# Main.net
KiCad netlist of a schematic drawn in Altium Designer
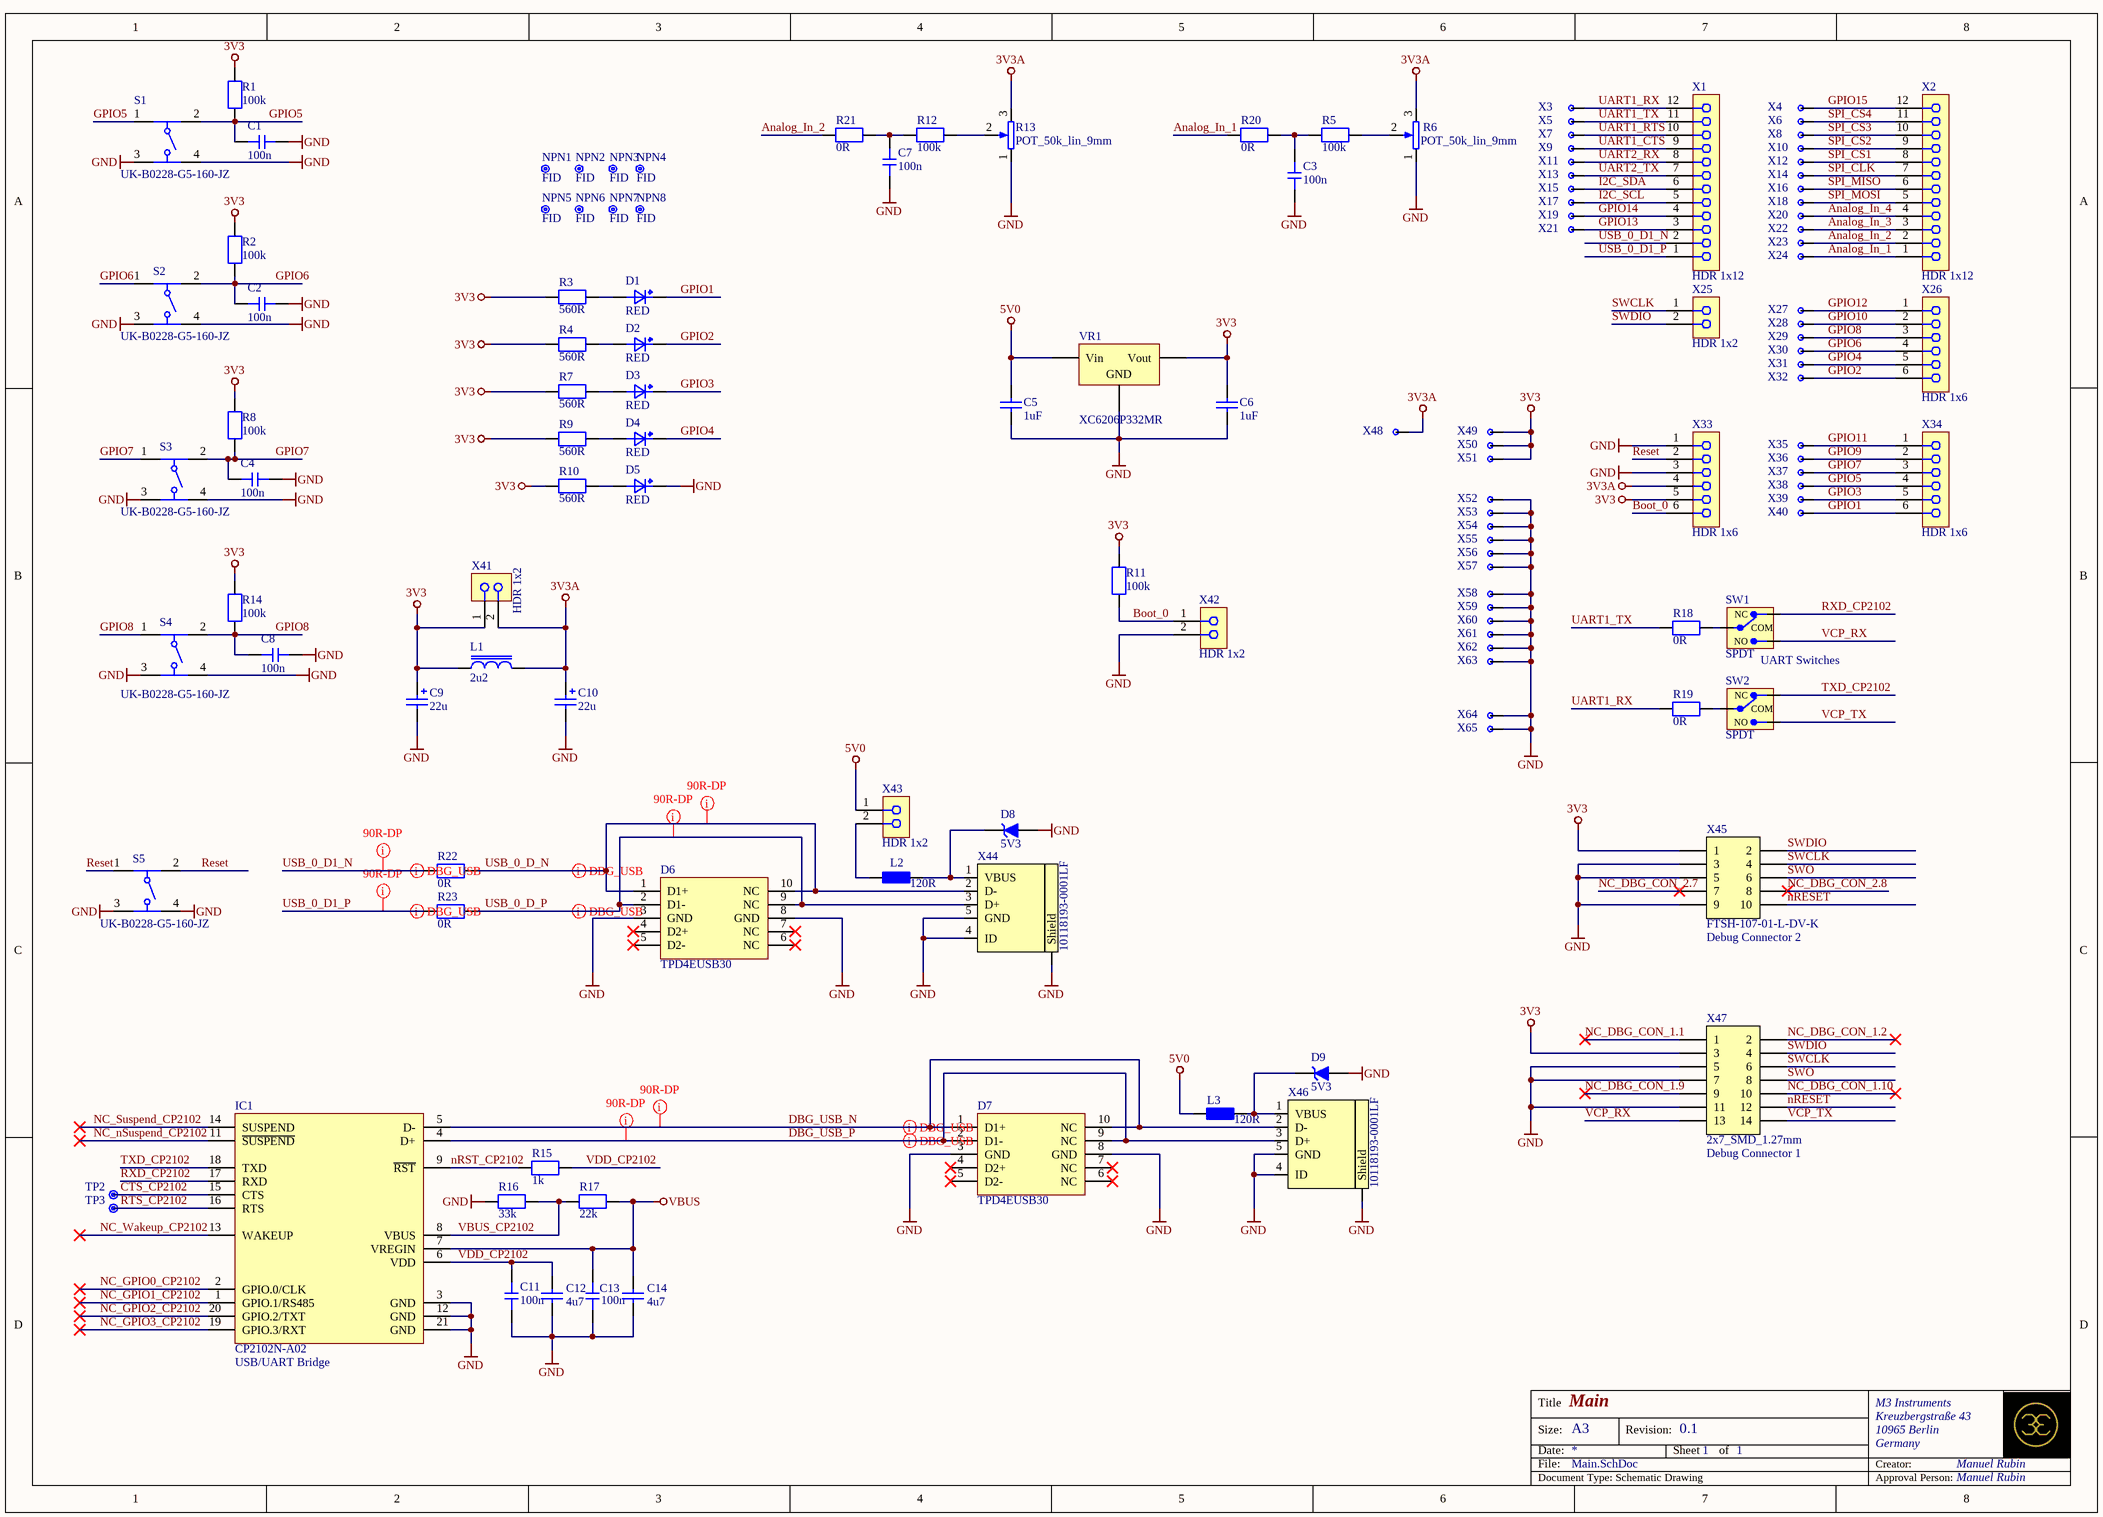
[diagram p0: Main.SchDoc]

(export (version "E")
  (design (tool "Eeschema 10.0.6"))
  (components
    (comp (ref "C1")
      (value "100n")
      (footprint "CAPC1608X95N")
      (description "100n_50V")
      (fields (field (name "MANUFACTURER") "AVX") (field (name "MANUFACTURER PART NUMBER") "06031C104KAT2A"))
      (libsource (lib "Raindancer") (part "C_100n_50V_0603"))
    )
    (comp (ref "C2")
      (value "100n")
      (footprint "CAPC1608X95N")
      (description "100n_50V")
      (fields (field (name "MANUFACTURER") "AVX") (field (name "MANUFACTURER PART NUMBER") "06031C104KAT2A"))
      (libsource (lib "Raindancer") (part "C_100n_50V_0603"))
    )
    (comp (ref "C3")
      (value "100n")
      (footprint "CAPC1608X95N")
      (description "100n_50V")
      (fields (field (name "MANUFACTURER") "AVX") (field (name "MANUFACTURER PART NUMBER") "06031C104KAT2A"))
      (libsource (lib "CAPN_100nF_50V_0603") (part "100n_50V"))
    )
    (comp (ref "C4")
      (value "100n")
      (footprint "CAPC1608X95N")
      (description "100n_50V")
      (fields (field (name "MANUFACTURER") "AVX") (field (name "MANUFACTURER PART NUMBER") "06031C104KAT2A"))
      (libsource (lib "Raindancer") (part "C_100n_50V_0603"))
    )
    (comp (ref "C5")
      (value "1uF")
      (footprint "0603_C")
      (description "Chip capacitors")
      (fields
        (field (name "MANUFACTURER") "Samsung Electro-Mechanics")
        (field (name "PARTNUMBER") "CL10A105KB8NNNC")
      )
      (libsource (lib "Cap") (part "0603 1uF (105) 10% 50V"))
    )
    (comp (ref "C6")
      (value "1uF")
      (footprint "0603_C")
      (description "Chip capacitors")
      (fields
        (field (name "MANUFACTURER") "Samsung Electro-Mechanics")
        (field (name "PARTNUMBER") "CL10A105KB8NNNC")
      )
      (libsource (lib "Cap") (part "0603 1uF (105) 10% 50V"))
    )
    (comp (ref "C7")
      (value "100n")
      (footprint "CAPC1608X95N")
      (description "100n_50V")
      (fields (field (name "MANUFACTURER") "AVX") (field (name "MANUFACTURER PART NUMBER") "06031C104KAT2A"))
      (libsource (lib "CAPN_100nF_50V_0603") (part "100n_50V"))
    )
    (comp (ref "C8")
      (value "100n")
      (footprint "CAPC1608X95N")
      (description "100n_50V")
      (fields (field (name "MANUFACTURER") "AVX") (field (name "MANUFACTURER PART NUMBER") "06031C104KAT2A"))
      (libsource (lib "Raindancer") (part "C_100n_50V_0603"))
    )
    (comp (ref "C9")
      (value "22u")
      (footprint "CAPAE4643X54M")
      (description "Aluminium Electrolytic Capacitors - SMD 22UF 16V HA SMD")
      (fields
        (field (name "MANUFACTURER") "Panasonic")
        (field (name "MANUFACTURER PART NUMBER") "EEE-HAC220WAR")
      )
      (libsource (lib "Caps") (part "CAP_22u"))
    )
    (comp (ref "C10")
      (value "22u")
      (footprint "CAPAE4643X54M")
      (description "Aluminium Electrolytic Capacitors - SMD 22UF 16V HA SMD")
      (fields
        (field (name "MANUFACTURER") "Panasonic")
        (field (name "MANUFACTURER PART NUMBER") "EEE-HAC220WAR")
      )
      (libsource (lib "Caps") (part "CAP_22u"))
    )
    (comp (ref "C11")
      (value "100n")
      (footprint "CAPC1608X95N")
      (description "100n_50V")
      (fields (field (name "MANUFACTURER") "AVX") (field (name "MANUFACTURER PART NUMBER") "06031C104KAT2A"))
      (libsource (lib "Raindancer") (part "C_100n_50V_0603"))
    )
    (comp (ref "C12")
      (value "4u7")
      (footprint "CAPC1608X95N")
      (description "16V 4.7uF X5R ±10% 0603 Multilayer Ceramic Capacitors MLCC - SMD/SMT ROHS")
      (fields
        (field (name "MANUFACTURER") "Murata Electronics")
        (field (name "MANUFACTURER PART NUMBER") "GRM188C81C475KE11D")
      )
      (libsource (lib "Caps") (part "CAP_4u7_0603"))
    )
    (comp (ref "C13")
      (value "100n")
      (footprint "CAPC1608X95N")
      (description "100n_50V")
      (fields (field (name "MANUFACTURER") "AVX") (field (name "MANUFACTURER PART NUMBER") "06031C104KAT2A"))
      (libsource (lib "Raindancer") (part "C_100n_50V_0603"))
    )
    (comp (ref "C14")
      (value "4u7")
      (footprint "CAPC1608X95N")
      (description "16V 4.7uF X5R ±10% 0603 Multilayer Ceramic Capacitors MLCC - SMD/SMT ROHS")
      (fields
        (field (name "MANUFACTURER") "Murata Electronics")
        (field (name "MANUFACTURER PART NUMBER") "GRM188C81C475KE11D")
      )
      (libsource (lib "Caps") (part "CAP_4u7_0603"))
    )
    (comp (ref "D1")
      (value "RED")
      (footprint "WL-SMCW_0805")
      (description "Standard LEDs - SMD WL-SMCW SMDMono TpVw Waterclr 0805 Red")
      (fields
        (field (name "MANUFACTURER") "Wurth Elektronik")
        (field (name "MANUFACTURER PART NUMBER") "150080RS75000")
      )
      (libsource (lib "Diodes") (part "LED_0805_RED_AK"))
    )
    (comp (ref "D2")
      (value "RED")
      (footprint "WL-SMCW_0805")
      (description "Standard LEDs - SMD WL-SMCW SMDMono TpVw Waterclr 0805 Red")
      (fields
        (field (name "MANUFACTURER") "Wurth Elektronik")
        (field (name "MANUFACTURER PART NUMBER") "150080RS75000")
      )
      (libsource (lib "Diodes") (part "LED_0805_RED_AK"))
    )
    (comp (ref "D3")
      (value "RED")
      (footprint "WL-SMCW_0805")
      (description "Standard LEDs - SMD WL-SMCW SMDMono TpVw Waterclr 0805 Red")
      (fields
        (field (name "MANUFACTURER") "Wurth Elektronik")
        (field (name "MANUFACTURER PART NUMBER") "150080RS75000")
      )
      (libsource (lib "Diodes") (part "LED_0805_RED_AK"))
    )
    (comp (ref "D4")
      (value "RED")
      (footprint "WL-SMCW_0805")
      (description "Standard LEDs - SMD WL-SMCW SMDMono TpVw Waterclr 0805 Red")
      (fields
        (field (name "MANUFACTURER") "Wurth Elektronik")
        (field (name "MANUFACTURER PART NUMBER") "150080RS75000")
      )
      (libsource (lib "Diodes") (part "LED_0805_RED_AK"))
    )
    (comp (ref "D5")
      (value "RED")
      (footprint "WL-SMCW_0805")
      (description "Standard LEDs - SMD WL-SMCW SMDMono TpVw Waterclr 0805 Red")
      (fields
        (field (name "MANUFACTURER") "Wurth Elektronik")
        (field (name "MANUFACTURER PART NUMBER") "150080RS75000")
      )
      (libsource (lib "Diodes") (part "LED_0805_RED_AK"))
    )
    (comp (ref "D6")
      (value "TPD4EUSB30")
      (footprint "DQA R-PUSON-N10")
      (description "2-, 4-Channel ESD Protection for Super-Speed USB 3.0 Interface")
      (fields
        (field (name "MANUFACTURER") "Texas Instruments")
        (field (name "MANUFACTURER PART NUMBER") "TPD4EUSB30DQAR")
      )
      (libsource (lib "TPD4EUSB30") (part "TPD4EUSB30DQAR"))
    )
    (comp (ref "D7")
      (value "TPD4EUSB30")
      (footprint "DQA R-PUSON-N10")
      (description "2-, 4-Channel ESD Protection for Super-Speed USB 3.0 Interface")
      (fields
        (field (name "MANUFACTURER") "Texas Instruments")
        (field (name "MANUFACTURER PART NUMBER") "TPD4EUSB30DQAR")
      )
      (libsource (lib "TPD4EUSB30") (part "TPD4EUSB30DQAR"))
    )
    (comp (ref "D8")
      (value "5V3")
      (footprint "SODFL100X40-2N")
      (description "ESD Suppressors / TVS Diodes WE-VE 0603 USB 2.0 5V 10MoHM")
      (fields
        (field (name "MANUFACTURER") "onsemi")
        (field (name "MANUFACTURER PART NUMBER") "SZESD7371P2T5G")
      )
      (libsource (lib "Diodes") (part "DIO_TVS_5V3"))
    )
    (comp (ref "D9")
      (value "5V3")
      (footprint "SODFL100X40-2N")
      (description "ESD Suppressors / TVS Diodes WE-VE 0603 USB 2.0 5V 10MoHM")
      (fields
        (field (name "MANUFACTURER") "onsemi")
        (field (name "MANUFACTURER PART NUMBER") "SZESD7371P2T5G")
      )
      (libsource (lib "Diodes") (part "DIO_TVS_5V3"))
    )
    (comp (ref "IC1")
      (value "CP2102N-A02")
      (footprint "SILABS_CP2102N-A02-GQFN20R")
      (description "USB Interface IC USBXpress - USB to UART Bridge QFN28")
      (fields
        (field (name "MANUFACTURER") "Silicon Labs")
        (field (name "MANUFACTURER PART NUMBER") "CP2102N-A02-GQFN20R")
        (field (name "DEVNOTE") "USB/UART Bridge")
      )
      (libsource (lib "Raindancer") (part "IC_CP2102N-A02-QFN20"))
    )
    (comp (ref "L1")
      (value "2u2")
      (footprint "INDP5050X39N")
      (description "Fixed Inductors 2.2uH 3.8A")
      (fields
        (field (name "MANUFACTURER") "Bourns")
        (field (name "MANUFACTURER PART NUMBER") "SRN5040TA-2R2M")
      )
      (libsource (lib "Inductors") (part "IND_2u2_3.8A"))
    )
    (comp (ref "L2")
      (value "120R")
      (footprint "INDC1608X95AN")
      (description "Chip Bead Inductors for Power Lines")
      (fields
        (field (name "MANUFACTURER") "Taiyo Yuden")
        (field (name "MANUFACTURER PART NUMBER") "FBMH1608HL121-T")
      )
      (libsource (lib "FB_120R_0603") (part "FB_120R_0603"))
    )
    (comp (ref "L3")
      (value "120R")
      (footprint "INDC1608X95AN")
      (description "Chip Bead Inductors for Power Lines")
      (fields
        (field (name "MANUFACTURER") "Taiyo Yuden")
        (field (name "MANUFACTURER PART NUMBER") "FBMH1608HL121-T")
      )
      (libsource (lib "FB_120R_0603") (part "FB_120R_0603"))
    )
    (comp (ref "NPN1")
      (value "FID")
      (footprint "Fiducial_1mm")
      (libsource (lib "MISC") (part "Fiducial_1mm"))
    )
    (comp (ref "NPN2")
      (value "FID")
      (footprint "Fiducial_1mm")
      (libsource (lib "MISC") (part "Fiducial_1mm"))
    )
    (comp (ref "NPN3")
      (value "FID")
      (footprint "Fiducial_1mm")
      (libsource (lib "MISC") (part "Fiducial_1mm"))
    )
    (comp (ref "NPN4")
      (value "FID")
      (footprint "Fiducial_1mm")
      (libsource (lib "MISC") (part "Fiducial_1mm"))
    )
    (comp (ref "NPN5")
      (value "FID")
      (footprint "Fiducial_1mm")
      (libsource (lib "MISC") (part "Fiducial_1mm"))
    )
    (comp (ref "NPN6")
      (value "FID")
      (footprint "Fiducial_1mm")
      (libsource (lib "MISC") (part "Fiducial_1mm"))
    )
    (comp (ref "NPN7")
      (value "FID")
      (footprint "Fiducial_1mm")
      (libsource (lib "MISC") (part "Fiducial_1mm"))
    )
    (comp (ref "NPN8")
      (value "FID")
      (footprint "Fiducial_1mm")
      (libsource (lib "MISC") (part "Fiducial_1mm"))
    )
    (comp (ref "R1")
      (value "100k")
      (footprint "RESC2012X70N")
      (description "Thick Film Resistors - SMD 1/8watt 100Kohms 1% 100ppm")
      (fields
        (field (name "MANUFACTURER") "Vishay / Dale")
        (field (name "MANUFACTURER PART NUMBER") "CRCW0805100KFKEA")
      )
      (libsource (lib "Resistors") (part "RES_100k_0805"))
    )
    (comp (ref "R2")
      (value "100k")
      (footprint "RESC2012X70N")
      (description "Thick Film Resistors - SMD 1/8watt 100Kohms 1% 100ppm")
      (fields
        (field (name "MANUFACTURER") "Vishay / Dale")
        (field (name "MANUFACTURER PART NUMBER") "CRCW0805100KFKEA")
      )
      (libsource (lib "Resistors") (part "RES_100k_0805"))
    )
    (comp (ref "R3")
      (value "560R")
      (footprint "RESC2012X70N")
      (description "Thick Film Resistors - SMD 560 Ohms 125 mW 0805 1%")
      (fields
        (field (name "MANUFACTURER") "YAGEO")
        (field (name "MANUFACTURER PART NUMBER") "RC0805FR-10560RL")
      )
      (libsource (lib "Resistors") (part "RES_560R_0805"))
    )
    (comp (ref "R4")
      (value "560R")
      (footprint "RESC2012X70N")
      (description "Thick Film Resistors - SMD 560 Ohms 125 mW 0805 1%")
      (fields
        (field (name "MANUFACTURER") "YAGEO")
        (field (name "MANUFACTURER PART NUMBER") "RC0805FR-10560RL")
      )
      (libsource (lib "Resistors") (part "RES_560R_0805"))
    )
    (comp (ref "R5")
      (value "100k")
      (footprint "RESC2012X70N")
      (description "Thick Film Resistors - SMD 1/8watt 100Kohms 1% 100ppm")
      (fields
        (field (name "MANUFACTURER") "Vishay / Dale")
        (field (name "MANUFACTURER PART NUMBER") "CRCW0805100KFKEA")
      )
      (libsource (lib "") (part "RES_100k_0805_1"))
    )
    (comp (ref "R6")
      (value "POT_50k_lin_9mm")
      (footprint "PTV09")
      (description "Potentiometers PANEL CONTROL - 9MM-ST-CA 50 kohms 30 mm")
      (fields
        (field (name "MANUFACTURER") "Bourns")
        (field (name "MANUFACTURER PART NUMBER") "PTV09A-4030S-A503")
      )
      (libsource (lib "Resistors") (part "POT_50k_lin_9mm"))
    )
    (comp (ref "R7")
      (value "560R")
      (footprint "RESC2012X70N")
      (description "Thick Film Resistors - SMD 560 Ohms 125 mW 0805 1%")
      (fields
        (field (name "MANUFACTURER") "YAGEO")
        (field (name "MANUFACTURER PART NUMBER") "RC0805FR-10560RL")
      )
      (libsource (lib "Resistors") (part "RES_560R_0805"))
    )
    (comp (ref "R8")
      (value "100k")
      (footprint "RESC2012X70N")
      (description "Thick Film Resistors - SMD 1/8watt 100Kohms 1% 100ppm")
      (fields
        (field (name "MANUFACTURER") "Vishay / Dale")
        (field (name "MANUFACTURER PART NUMBER") "CRCW0805100KFKEA")
      )
      (libsource (lib "Resistors") (part "RES_100k_0805"))
    )
    (comp (ref "R9")
      (value "560R")
      (footprint "RESC2012X70N")
      (description "Thick Film Resistors - SMD 560 Ohms 125 mW 0805 1%")
      (fields
        (field (name "MANUFACTURER") "YAGEO")
        (field (name "MANUFACTURER PART NUMBER") "RC0805FR-10560RL")
      )
      (libsource (lib "Resistors") (part "RES_560R_0805"))
    )
    (comp (ref "R10")
      (value "560R")
      (footprint "RESC2012X70N")
      (description "Thick Film Resistors - SMD 560 Ohms 125 mW 0805 1%")
      (fields
        (field (name "MANUFACTURER") "YAGEO")
        (field (name "MANUFACTURER PART NUMBER") "RC0805FR-10560RL")
      )
      (libsource (lib "Resistors") (part "RES_560R_0805"))
    )
    (comp (ref "R11")
      (value "100k")
      (footprint "RESC2012X70N")
      (description "Thick Film Resistors - SMD 1/8watt 100Kohms 1% 100ppm")
      (fields
        (field (name "MANUFACTURER") "Vishay / Dale")
        (field (name "MANUFACTURER PART NUMBER") "CRCW0805100KFKEA")
      )
      (libsource (lib "Resistors") (part "RES_100k_0805"))
    )
    (comp (ref "R12")
      (value "100k")
      (footprint "RESC2012X70N")
      (description "Thick Film Resistors - SMD 1/8watt 100Kohms 1% 100ppm")
      (fields
        (field (name "MANUFACTURER") "Vishay / Dale")
        (field (name "MANUFACTURER PART NUMBER") "CRCW0805100KFKEA")
      )
      (libsource (lib "") (part "RES_100k_0805_1"))
    )
    (comp (ref "R13")
      (value "POT_50k_lin_9mm")
      (footprint "PTV09")
      (description "Potentiometers PANEL CONTROL - 9MM-ST-CA 50 kohms 30 mm")
      (fields
        (field (name "MANUFACTURER") "Bourns")
        (field (name "MANUFACTURER PART NUMBER") "PTV09A-4030S-A503")
      )
      (libsource (lib "Resistors") (part "POT_50k_lin_9mm"))
    )
    (comp (ref "R14")
      (value "100k")
      (footprint "RESC2012X70N")
      (description "Thick Film Resistors - SMD 1/8watt 100Kohms 1% 100ppm")
      (fields
        (field (name "MANUFACTURER") "Vishay / Dale")
        (field (name "MANUFACTURER PART NUMBER") "CRCW0805100KFKEA")
      )
      (libsource (lib "Resistors") (part "RES_100k_0805"))
    )
    (comp (ref "R15")
      (value "1k")
      (footprint "RESC1608X55AN")
      (description "Thick Film Resistors - SMD 1 kOhms 100mW 0603 1%")
      (fields
        (field (name "MANUFACTURER") "Yageo")
        (field (name "MANUFACTURER PART NUMBER") "RC0603FR-071KL")
      )
      (libsource (lib "Raindancer") (part "RES_1k_0603"))
    )
    (comp (ref "R16")
      (value "33k")
      (footprint "RESC1608X55AN")
      (description "Thick Film Resistors - SMD 33 kOhms 100 mW 0603 5%")
      (fields
        (field (name "MANUFACTURER") "YAGEO")
        (field (name "MANUFACTURER PART NUMBER") "RC0603JR-0733KL")
      )
      (libsource (lib "Raindancer") (part "RES_33k_0603"))
    )
    (comp (ref "R17")
      (value "22k")
      (footprint "RESC1608X55AN")
      (description "Thick Film Resistors - SMD 22kOhms 1/10W 0603 1%")
      (fields
        (field (name "MANUFACTURER") "YAGEO")
        (field (name "MANUFACTURER PART NUMBER") "RC0603FR-7W22KL")
      )
      (libsource (lib "Raindancer") (part "RES_22k_0603"))
    )
    (comp (ref "R18")
      (value "0R")
      (footprint "RESC1608X55N")
      (description "Thick Film Resistors - SMD 1/10watt ZEROohm Jumper")
      (fields
        (field (name "MANUFACTURER") "Vishay")
        (field (name "MANUFACTURER PART NUMBER") "CRCW06030000Z0EA")
      )
      (libsource (lib "Resistors") (part "RES_0R_0603"))
    )
    (comp (ref "R19")
      (value "0R")
      (footprint "RESC1608X55N")
      (description "Thick Film Resistors - SMD 1/10watt ZEROohm Jumper")
      (fields
        (field (name "MANUFACTURER") "Vishay")
        (field (name "MANUFACTURER PART NUMBER") "CRCW06030000Z0EA")
      )
      (libsource (lib "Resistors") (part "RES_0R_0603"))
    )
    (comp (ref "R20")
      (value "0R")
      (footprint "RESC1608X55N")
      (description "Thick Film Resistors - SMD 1/10watt ZEROohm Jumper")
      (fields
        (field (name "MANUFACTURER") "Vishay")
        (field (name "MANUFACTURER PART NUMBER") "CRCW06030000Z0EA")
      )
      (libsource (lib "Resistors") (part "RES_0R_0603"))
    )
    (comp (ref "R21")
      (value "0R")
      (footprint "RESC1608X55N")
      (description "Thick Film Resistors - SMD 1/10watt ZEROohm Jumper")
      (fields
        (field (name "MANUFACTURER") "Vishay")
        (field (name "MANUFACTURER PART NUMBER") "CRCW06030000Z0EA")
      )
      (libsource (lib "Resistors") (part "RES_0R_0603"))
    )
    (comp (ref "R22")
      (value "0R")
      (footprint "RESC1608X55N")
      (description "Thick Film Resistors - SMD 1/10watt ZEROohm Jumper")
      (fields
        (field (name "MANUFACTURER") "Vishay")
        (field (name "MANUFACTURER PART NUMBER") "CRCW06030000Z0EA")
      )
      (libsource (lib "Resistors") (part "RES_0R_0603"))
    )
    (comp (ref "R23")
      (value "0R")
      (footprint "RESC1608X55N")
      (description "Thick Film Resistors - SMD 1/10watt ZEROohm Jumper")
      (fields
        (field (name "MANUFACTURER") "Vishay")
        (field (name "MANUFACTURER PART NUMBER") "CRCW06030000Z0EA")
      )
      (libsource (lib "Resistors") (part "RES_0R_0603"))
    )
    (comp (ref "S1")
      (value "UK-B0228-G5-160-JZ")
      (footprint "UK-B0228-G5-160-JZ")
      (fields (field (name "MANUFACTURER") "USAKRO"))
      (libsource (lib "Switches") (part "SW_UK-B0228-G5-160-JZ"))
    )
    (comp (ref "S2")
      (value "UK-B0228-G5-160-JZ")
      (footprint "UK-B0228-G5-160-JZ")
      (fields (field (name "MANUFACTURER") "USAKRO"))
      (libsource (lib "Switches") (part "SW_UK-B0228-G5-160-JZ"))
    )
    (comp (ref "S3")
      (value "UK-B0228-G5-160-JZ")
      (footprint "UK-B0228-G5-160-JZ")
      (fields (field (name "MANUFACTURER") "USAKRO"))
      (libsource (lib "Switches") (part "SW_UK-B0228-G5-160-JZ"))
    )
    (comp (ref "S4")
      (value "UK-B0228-G5-160-JZ")
      (footprint "UK-B0228-G5-160-JZ")
      (fields (field (name "MANUFACTURER") "USAKRO"))
      (libsource (lib "Switches") (part "SW_UK-B0228-G5-160-JZ"))
    )
    (comp (ref "S5")
      (value "UK-B0228-G5-160-JZ")
      (footprint "UK-B0228-G5-160-JZ")
      (fields (field (name "MANUFACTURER") "USAKRO"))
      (libsource (lib "Switches") (part "SW_UK-B0228-G5-160-JZ"))
    )
    (comp (ref "SW1")
      (value "SPDT")
      (footprint "SW_JS102011JCQN")
      (description "Slide Switch SPDT Surface Mount")
      (fields
        (field (name "MANUFACTURER") "C&K")
        (field (name "MANUFACTURER PART NUMBER") "JS102011JCQN")
        (field (name "DEVNOTE") "UART Switches")
      )
      (libsource (lib "Raindancer") (part "SW_JS102011JCQN"))
    )
    (comp (ref "SW2")
      (value "SPDT")
      (footprint "SW_JS102011JCQN")
      (description "Slide Switch SPDT Surface Mount")
      (fields (field (name "MANUFACTURER") "C&K") (field (name "MANUFACTURER PART NUMBER") "JS102011JCQN"))
      (libsource (lib "Raindancer") (part "SW_JS102011JCQN"))
    )
    (comp (ref "TP2")
      (value "TP 0.7mm")
      (footprint "TP_0.7mm")
      (description "Test Pad surface mount")
      (libsource (lib "Raindancer") (part "MISC_Test Pad 0.7mm"))
    )
    (comp (ref "TP3")
      (value "TP 0.7mm")
      (footprint "TP_0.7mm")
      (description "Test Pad surface mount")
      (libsource (lib "Raindancer") (part "MISC_Test Pad 0.7mm"))
    )
    (comp (ref "VR1")
      (value "XC6206P332MR")
      (footprint "SOT-23-3L")
      (description "低压差线性稳压(LDO)")
      (libsource (lib "LDO") (part "SOT-23 XC6206P332MR"))
    )
    (comp (ref "X1")
      (value "HDR 1x12")
      (footprint "61301211821_NO")
      (description "Board-to-Board-Steckverbinder, 2.54 mm, 12 Kontakt(e), Stiftleiste 1-Reihig")
      (fields (field (name "MANUFACTURER") "WE") (field (name "MANUFACTURER PART NUMBER") "61301211821"))
      (libsource (lib "Connectors") (part "CON_HEADER_1X12_FEMALE_NO"))
    )
    (comp (ref "X2")
      (value "HDR 1x12")
      (footprint "61301211821_NO")
      (description "Board-to-Board-Steckverbinder, 2.54 mm, 12 Kontakt(e), Stiftleiste 1-Reihig")
      (fields (field (name "MANUFACTURER") "WE") (field (name "MANUFACTURER PART NUMBER") "61301211821"))
      (libsource (lib "Connectors") (part "CON_HEADER_1X12_FEMALE_NO"))
    )
    (comp (ref "X3") (value "PAD") (footprint "PAD_1.1_1.6") (libsource (lib "MISC") (part "PAD_2.54")))
    (comp (ref "X4") (value "PAD") (footprint "PAD_1.1_1.6") (libsource (lib "MISC") (part "PAD_2.54")))
    (comp (ref "X5") (value "PAD") (footprint "PAD_1.1_1.6") (libsource (lib "MISC") (part "PAD_2.54")))
    (comp (ref "X6") (value "PAD") (footprint "PAD_1.1_1.6") (libsource (lib "MISC") (part "PAD_2.54")))
    (comp (ref "X7") (value "PAD") (footprint "PAD_1.1_1.6") (libsource (lib "MISC") (part "PAD_2.54")))
    (comp (ref "X8") (value "PAD") (footprint "PAD_1.1_1.6") (libsource (lib "MISC") (part "PAD_2.54")))
    (comp (ref "X9") (value "PAD") (footprint "PAD_1.1_1.6") (libsource (lib "MISC") (part "PAD_2.54")))
    (comp (ref "X10") (value "PAD") (footprint "PAD_1.1_1.6") (libsource (lib "MISC") (part "PAD_2.54")))
    (comp (ref "X11") (value "PAD") (footprint "PAD_1.1_1.6") (libsource (lib "MISC") (part "PAD_2.54")))
    (comp (ref "X12") (value "PAD") (footprint "PAD_1.1_1.6") (libsource (lib "MISC") (part "PAD_2.54")))
    (comp (ref "X13") (value "PAD") (footprint "PAD_1.1_1.6") (libsource (lib "MISC") (part "PAD_2.54")))
    (comp (ref "X14") (value "PAD") (footprint "PAD_1.1_1.6") (libsource (lib "MISC") (part "PAD_2.54")))
    (comp (ref "X15") (value "PAD") (footprint "PAD_1.1_1.6") (libsource (lib "MISC") (part "PAD_2.54")))
    (comp (ref "X16") (value "PAD") (footprint "PAD_1.1_1.6") (libsource (lib "MISC") (part "PAD_2.54")))
    (comp (ref "X17") (value "PAD") (footprint "PAD_1.1_1.6") (libsource (lib "MISC") (part "PAD_2.54")))
    (comp (ref "X18") (value "PAD") (footprint "PAD_1.1_1.6") (libsource (lib "MISC") (part "PAD_2.54")))
    (comp (ref "X19") (value "PAD") (footprint "PAD_1.1_1.6") (libsource (lib "MISC") (part "PAD_2.54")))
    (comp (ref "X20") (value "PAD") (footprint "PAD_1.1_1.6") (libsource (lib "MISC") (part "PAD_2.54")))
    (comp (ref "X21") (value "PAD") (footprint "PAD_1.1_1.6") (libsource (lib "MISC") (part "PAD_2.54")))
    (comp (ref "X22") (value "PAD") (footprint "PAD_1.1_1.6") (libsource (lib "MISC") (part "PAD_2.54")))
    (comp (ref "X23") (value "PAD") (footprint "PAD_1.1_1.6") (libsource (lib "MISC") (part "PAD_2.54")))
    (comp (ref "X24") (value "PAD") (footprint "PAD_1.1_1.6") (libsource (lib "MISC") (part "PAD_2.54")))
    (comp (ref "X25")
      (value "HDR 1x2")
      (footprint "61300211821_NO")
      (description "Board-to-Board-Steckverbinder, 2.54 mm, 2 Kontakt(e), Stiftleiste 1-Reihig")
      (fields (field (name "MANUFACTURER") "WE") (field (name "MANUFACTURER PART NUMBER") "61300211821"))
      (libsource (lib "Connectors") (part "CON_HEADER_1X2_FEMALE_NO"))
    )
    (comp (ref "X26")
      (value "HDR 1x6")
      (footprint "61300611821_NO")
      (description "Board-to-Board-Steckverbinder, 2.54 mm, 6 Kontakt(e), Stiftleiste 1-Reihig")
      (fields (field (name "MANUFACTURER") "WE") (field (name "MANUFACTURER PART NUMBER") "61300611821"))
      (libsource (lib "Connectors") (part "CON_HEADER_1X6_FEMALE_NO"))
    )
    (comp (ref "X27") (value "PAD") (footprint "PAD_1.1_1.6") (libsource (lib "MISC") (part "PAD_2.54")))
    (comp (ref "X28") (value "PAD") (footprint "PAD_1.1_1.6") (libsource (lib "MISC") (part "PAD_2.54")))
    (comp (ref "X29") (value "PAD") (footprint "PAD_1.1_1.6") (libsource (lib "MISC") (part "PAD_2.54")))
    (comp (ref "X30") (value "PAD") (footprint "PAD_1.1_1.6") (libsource (lib "MISC") (part "PAD_2.54")))
    (comp (ref "X31") (value "PAD") (footprint "PAD_1.1_1.6") (libsource (lib "MISC") (part "PAD_2.54")))
    (comp (ref "X32") (value "PAD") (footprint "PAD_1.1_1.6") (libsource (lib "MISC") (part "PAD_2.54")))
    (comp (ref "X33")
      (value "HDR 1x6")
      (footprint "61300611821_NO")
      (description "Board-to-Board-Steckverbinder, 2.54 mm, 6 Kontakt(e), Stiftleiste 1-Reihig")
      (fields (field (name "MANUFACTURER") "WE") (field (name "MANUFACTURER PART NUMBER") "61300611821"))
      (libsource (lib "Connectors") (part "CON_HEADER_1X6_FEMALE_NO"))
    )
    (comp (ref "X34")
      (value "HDR 1x6")
      (footprint "61300611821_NO")
      (description "Board-to-Board-Steckverbinder, 2.54 mm, 6 Kontakt(e), Stiftleiste 1-Reihig")
      (fields (field (name "MANUFACTURER") "WE") (field (name "MANUFACTURER PART NUMBER") "61300611821"))
      (libsource (lib "Connectors") (part "CON_HEADER_1X6_FEMALE_NO"))
    )
    (comp (ref "X35") (value "PAD") (footprint "PAD_1.1_1.6") (libsource (lib "MISC") (part "PAD_2.54")))
    (comp (ref "X36") (value "PAD") (footprint "PAD_1.1_1.6") (libsource (lib "MISC") (part "PAD_2.54")))
    (comp (ref "X37") (value "PAD") (footprint "PAD_1.1_1.6") (libsource (lib "MISC") (part "PAD_2.54")))
    (comp (ref "X38") (value "PAD") (footprint "PAD_1.1_1.6") (libsource (lib "MISC") (part "PAD_2.54")))
    (comp (ref "X39") (value "PAD") (footprint "PAD_1.1_1.6") (libsource (lib "MISC") (part "PAD_2.54")))
    (comp (ref "X40") (value "PAD") (footprint "PAD_1.1_1.6") (libsource (lib "MISC") (part "PAD_2.54")))
    (comp (ref "X41")
      (value "HDR 1x2")
      (footprint "CON_HEADER2.54_1x2W")
      (description "Board-to-Board-Steckverbinder, 2.54 mm, 2 Kontakt(e), Stiftleiste 1-Reihig")
      (fields
        (field (name "MANUFACTURER") "Samtec")
        (field (name "MANUFACTURER PART NUMBER") "TSW-102-07-T-S")
      )
      (libsource (lib "") (part "CON_HEADER_1X2_1"))
    )
    (comp (ref "X42")
      (value "HDR 1x2")
      (footprint "CON_HEADER2.54_1x2W")
      (description "Board-to-Board-Steckverbinder, 2.54 mm, 2 Kontakt(e), Stiftleiste 1-Reihig")
      (fields
        (field (name "MANUFACTURER") "Samtec")
        (field (name "MANUFACTURER PART NUMBER") "TSW-102-07-T-S")
      )
      (libsource (lib "Connectors") (part "CON_HEADER_1X2"))
    )
    (comp (ref "X43")
      (value "HDR 1x2")
      (footprint "CON_HEADER2.54_1x2W")
      (description "Board-to-Board-Steckverbinder, 2.54 mm, 2 Kontakt(e), Stiftleiste 1-Reihig")
      (fields
        (field (name "MANUFACTURER") "Samtec")
        (field (name "MANUFACTURER PART NUMBER") "TSW-102-07-T-S")
      )
      (libsource (lib "Connectors") (part "CON_HEADER_1X2"))
    )
    (comp (ref "X44")
      (value "10118193-0001LF")
      (footprint "USB-Micro-B-RA-SMD-PiP")
      (description "MicroUSB-B-SMT")
      (fields (field (name "MANUFACTURER") "Amphenol ICC (FCI)"))
      (libsource (lib "Connectors") (part "CON_MiniUSB-AB-SMT"))
    )
    (comp (ref "X45")
      (value "FTSH-107-01-L-DV-K")
      (footprint "HDR_2x5-SMD-1.27mm-K")
      (description "Pin Header 2x5, 1.27mm (50mil), SMD, Keying Shroud")
      (fields
        (field (name "MANUFACTURER") "Samtec")
        (field (name "MANUFACTURER PART NUMBER") "FTSH-105-01-L-DV-K")
        (field (name "DEVNOTE") "Debug Connector 2")
      )
      (libsource (lib "Raindancer") (part "CON_2x5_SMD_1.27mm"))
    )
    (comp (ref "X46")
      (value "10118193-0001LF")
      (footprint "USB-Micro-B-RA-SMD-PiP")
      (description "MicroUSB-B-SMT")
      (fields (field (name "MANUFACTURER") "Amphenol ICC (FCI)"))
      (libsource (lib "Connectors") (part "CON_MiniUSB-AB-SMT"))
    )
    (comp (ref "X47")
      (value "2x7_SMD_1.27mm")
      (footprint "FTSH-107-01-L-DV-K")
      (description "Headers & Wire Housings High Reliability Header Strips, 0.050 pitch, 2 x 7")
      (fields
        (field (name "MANUFACTURER") "Samtec")
        (field (name "MANUFACTURER PART NUMBER") "FTSH-107-04-F-DV-P-TR")
        (field (name "DEVNOTE") "Debug Connector 1")
      )
      (libsource (lib "Raindancer") (part "CON_2x7_SMD_1.27mm"))
    )
    (comp (ref "X48") (value "PAD") (footprint "PAD_1.1_1.6") (libsource (lib "MISC") (part "PAD_2.54")))
    (comp (ref "X49") (value "PAD") (footprint "PAD_1.1_1.6") (libsource (lib "MISC") (part "PAD_2.54")))
    (comp (ref "X50") (value "PAD") (footprint "PAD_1.1_1.6") (libsource (lib "MISC") (part "PAD_2.54")))
    (comp (ref "X51") (value "PAD") (footprint "PAD_1.1_1.6") (libsource (lib "MISC") (part "PAD_2.54")))
    (comp (ref "X52") (value "PAD") (footprint "PAD_1.1_1.6") (libsource (lib "MISC") (part "PAD_2.54")))
    (comp (ref "X53") (value "PAD") (footprint "PAD_1.1_1.6") (libsource (lib "MISC") (part "PAD_2.54")))
    (comp (ref "X54") (value "PAD") (footprint "PAD_1.1_1.6") (libsource (lib "MISC") (part "PAD_2.54")))
    (comp (ref "X55") (value "PAD") (footprint "PAD_1.1_1.6") (libsource (lib "MISC") (part "PAD_2.54")))
    (comp (ref "X56") (value "PAD") (footprint "PAD_1.1_1.6") (libsource (lib "MISC") (part "PAD_2.54")))
    (comp (ref "X57") (value "PAD") (footprint "PAD_1.1_1.6") (libsource (lib "MISC") (part "PAD_2.54")))
    (comp (ref "X58") (value "PAD") (footprint "PAD_1.1_1.6") (libsource (lib "MISC") (part "PAD_2.54")))
    (comp (ref "X59") (value "PAD") (footprint "PAD_1.1_1.6") (libsource (lib "MISC") (part "PAD_2.54")))
    (comp (ref "X60") (value "PAD") (footprint "PAD_1.1_1.6") (libsource (lib "MISC") (part "PAD_2.54")))
    (comp (ref "X61") (value "PAD") (footprint "PAD_1.1_1.6") (libsource (lib "MISC") (part "PAD_2.54")))
    (comp (ref "X62") (value "PAD") (footprint "PAD_1.1_1.6") (libsource (lib "MISC") (part "PAD_2.54")))
    (comp (ref "X63") (value "PAD") (footprint "PAD_1.1_1.6") (libsource (lib "MISC") (part "PAD_2.54")))
    (comp (ref "X64") (value "PAD") (footprint "PAD_1.1_1.6") (libsource (lib "MISC") (part "PAD_2.54")))
    (comp (ref "X65") (value "PAD") (footprint "PAD_1.1_1.6") (libsource (lib "MISC") (part "PAD_2.54")))
  )
  (nets
    (net (code "1") (name "/Analog_In_1") (class "Default")
      (node (ref "R20") (pin "2") (pinfunction "2_2") (pintype "passive"))
      (node (ref "X2") (pin "1") (pinfunction "1_1") (pintype "passive"))
      (node (ref "X24") (pin "1") (pinfunction "1_1") (pintype "passive"))
    )
    (net (code "2") (name "/Analog_In_2") (class "Default")
      (node (ref "R21") (pin "2") (pinfunction "2_2") (pintype "passive"))
      (node (ref "X2") (pin "2") (pinfunction "2_2") (pintype "passive"))
      (node (ref "X23") (pin "1") (pinfunction "1_1") (pintype "passive"))
    )
    (net (code "3") (name "/Analog_In_3") (class "Default")
      (node (ref "X2") (pin "3") (pinfunction "3_3") (pintype "passive"))
      (node (ref "X22") (pin "1") (pinfunction "1_1") (pintype "passive"))
    )
    (net (code "4") (name "/Analog_In_4") (class "Default")
      (node (ref "X2") (pin "4") (pinfunction "4_4") (pintype "passive"))
      (node (ref "X20") (pin "1") (pinfunction "1_1") (pintype "passive"))
    )
    (net (code "5") (name "/Boot_0") (class "Default")
      (node (ref "R11") (pin "1") (pinfunction "1_1") (pintype "passive"))
      (node (ref "X33") (pin "6") (pinfunction "6_6") (pintype "passive"))
      (node (ref "X42") (pin "1") (pinfunction "1_1") (pintype "passive"))
    )
    (net (code "6") (name "/CTS_CP2102") (class "Default")
      (node (ref "IC1") (pin "15") (pinfunction "CTS_15") (pintype "passive"))
      (node (ref "TP2") (pin "1") (pinfunction "1_1") (pintype "passive"))
    )
    (net (code "7") (name "/DBG_USB_N") (class "Default")
      (node (ref "D7") (pin "1") (pinfunction "D1+_1") (pintype "passive"))
      (node (ref "D7") (pin "10") (pinfunction "NC_10") (pintype "passive"))
      (node (ref "IC1") (pin "5") (pinfunction "D-_5") (pintype "passive"))
      (node (ref "X46") (pin "2") (pinfunction "D-_2") (pintype "passive"))
    )
    (net (code "8") (name "/DBG_USB_P") (class "Default")
      (node (ref "D7") (pin "2") (pinfunction "D1-_2") (pintype "passive"))
      (node (ref "D7") (pin "9") (pinfunction "NC_9") (pintype "passive"))
      (node (ref "IC1") (pin "4") (pinfunction "D+_4") (pintype "passive"))
      (node (ref "X46") (pin "3") (pinfunction "D+_3") (pintype "passive"))
    )
    (net (code "9") (name "/GPIO1") (class "Default")
      (node (ref "D1") (pin "K") (pinfunction "K_K") (pintype "passive"))
      (node (ref "X34") (pin "6") (pinfunction "6_6") (pintype "passive"))
      (node (ref "X40") (pin "1") (pinfunction "1_1") (pintype "passive"))
    )
    (net (code "10") (name "/GPIO2") (class "Default")
      (node (ref "D2") (pin "K") (pinfunction "K_K") (pintype "passive"))
      (node (ref "X26") (pin "6") (pinfunction "6_6") (pintype "passive"))
      (node (ref "X32") (pin "1") (pinfunction "1_1") (pintype "passive"))
    )
    (net (code "11") (name "/GPIO3") (class "Default")
      (node (ref "D3") (pin "K") (pinfunction "K_K") (pintype "passive"))
      (node (ref "X34") (pin "5") (pinfunction "5_5") (pintype "passive"))
      (node (ref "X39") (pin "1") (pinfunction "1_1") (pintype "passive"))
    )
    (net (code "12") (name "/GPIO4") (class "Default")
      (node (ref "D4") (pin "K") (pinfunction "K_K") (pintype "passive"))
      (node (ref "X26") (pin "5") (pinfunction "5_5") (pintype "passive"))
      (node (ref "X31") (pin "1") (pinfunction "1_1") (pintype "passive"))
    )
    (net (code "13") (name "/GPIO5") (class "Default")
      (node (ref "C1") (pin "1") (pinfunction "1_1") (pintype "passive"))
      (node (ref "R1") (pin "1") (pinfunction "1_1") (pintype "passive"))
      (node (ref "S1") (pin "1") (pinfunction "1_1") (pintype "passive"))
      (node (ref "S1") (pin "2") (pinfunction "2_2") (pintype "passive"))
      (node (ref "X34") (pin "4") (pinfunction "4_4") (pintype "passive"))
      (node (ref "X38") (pin "1") (pinfunction "1_1") (pintype "passive"))
    )
    (net (code "14") (name "/GPIO6") (class "Default")
      (node (ref "C2") (pin "1") (pinfunction "1_1") (pintype "passive"))
      (node (ref "R2") (pin "1") (pinfunction "1_1") (pintype "passive"))
      (node (ref "S2") (pin "1") (pinfunction "1_1") (pintype "passive"))
      (node (ref "S2") (pin "2") (pinfunction "2_2") (pintype "passive"))
      (node (ref "X26") (pin "4") (pinfunction "4_4") (pintype "passive"))
      (node (ref "X30") (pin "1") (pinfunction "1_1") (pintype "passive"))
    )
    (net (code "15") (name "/GPIO7") (class "Default")
      (node (ref "C4") (pin "1") (pinfunction "1_1") (pintype "passive"))
      (node (ref "R8") (pin "1") (pinfunction "1_1") (pintype "passive"))
      (node (ref "S3") (pin "1") (pinfunction "1_1") (pintype "passive"))
      (node (ref "S3") (pin "2") (pinfunction "2_2") (pintype "passive"))
      (node (ref "X34") (pin "3") (pinfunction "3_3") (pintype "passive"))
      (node (ref "X37") (pin "1") (pinfunction "1_1") (pintype "passive"))
    )
    (net (code "16") (name "/GPIO8") (class "Default")
      (node (ref "C8") (pin "1") (pinfunction "1_1") (pintype "passive"))
      (node (ref "R14") (pin "1") (pinfunction "1_1") (pintype "passive"))
      (node (ref "S4") (pin "1") (pinfunction "1_1") (pintype "passive"))
      (node (ref "S4") (pin "2") (pinfunction "2_2") (pintype "passive"))
      (node (ref "X26") (pin "3") (pinfunction "3_3") (pintype "passive"))
      (node (ref "X29") (pin "1") (pinfunction "1_1") (pintype "passive"))
    )
    (net (code "17") (name "/GPIO9") (class "Default")
      (node (ref "X34") (pin "2") (pinfunction "2_2") (pintype "passive"))
      (node (ref "X36") (pin "1") (pinfunction "1_1") (pintype "passive"))
    )
    (net (code "18") (name "/GPIO10") (class "Default")
      (node (ref "X26") (pin "2") (pinfunction "2_2") (pintype "passive"))
      (node (ref "X28") (pin "1") (pinfunction "1_1") (pintype "passive"))
    )
    (net (code "19") (name "/GPIO11") (class "Default")
      (node (ref "X34") (pin "1") (pinfunction "1_1") (pintype "passive"))
      (node (ref "X35") (pin "1") (pinfunction "1_1") (pintype "passive"))
    )
    (net (code "20") (name "/GPIO12") (class "Default")
      (node (ref "X26") (pin "1") (pinfunction "1_1") (pintype "passive"))
      (node (ref "X27") (pin "1") (pinfunction "1_1") (pintype "passive"))
    )
    (net (code "21") (name "/GPIO13") (class "Default")
      (node (ref "X1") (pin "3") (pinfunction "3_3") (pintype "passive"))
      (node (ref "X21") (pin "1") (pinfunction "1_1") (pintype "passive"))
    )
    (net (code "22") (name "/GPIO14") (class "Default")
      (node (ref "X1") (pin "4") (pinfunction "4_4") (pintype "passive"))
      (node (ref "X19") (pin "1") (pinfunction "1_1") (pintype "passive"))
    )
    (net (code "23") (name "/GPIO15") (class "Default")
      (node (ref "X2") (pin "12") (pinfunction "12_12") (pintype "passive"))
      (node (ref "X4") (pin "1") (pinfunction "1_1") (pintype "passive"))
    )
    (net (code "24") (name "/I2C_SCL") (class "Default")
      (node (ref "X1") (pin "5") (pinfunction "5_5") (pintype "passive"))
      (node (ref "X17") (pin "1") (pinfunction "1_1") (pintype "passive"))
    )
    (net (code "25") (name "/I2C_SDA") (class "Default")
      (node (ref "X1") (pin "6") (pinfunction "6_6") (pintype "passive"))
      (node (ref "X15") (pin "1") (pinfunction "1_1") (pintype "passive"))
    )
    (net (code "26") (name "/NC_DBG_CON_1.1") (class "Default")
      (node (ref "X47") (pin "1") (pinfunction "1_1") (pintype "passive+no_connect"))
    )
    (net (code "27") (name "/NC_DBG_CON_1.2") (class "Default")
      (node (ref "X47") (pin "2") (pinfunction "2_2") (pintype "passive+no_connect"))
    )
    (net (code "28") (name "/NC_DBG_CON_1.9") (class "Default")
      (node (ref "X47") (pin "9") (pinfunction "9_9") (pintype "passive+no_connect"))
    )
    (net (code "29") (name "/NC_DBG_CON_1.10") (class "Default")
      (node (ref "X47") (pin "10") (pinfunction "10_10") (pintype "passive+no_connect"))
    )
    (net (code "30") (name "/NC_DBG_CON_2.7") (class "Default")
      (node (ref "X45") (pin "7") (pinfunction "7_7") (pintype "passive+no_connect"))
    )
    (net (code "31") (name "/NC_DBG_CON_2.8") (class "Default")
      (node (ref "X45") (pin "8") (pinfunction "8_8") (pintype "passive+no_connect"))
    )
    (net (code "32") (name "/NC_GPIO0_CP2102") (class "Default")
      (node (ref "IC1") (pin "2") (pinfunction "GPIO.0/CLK_2") (pintype "passive+no_connect"))
    )
    (net (code "33") (name "/NC_GPIO1_CP2102") (class "Default")
      (node (ref "IC1") (pin "1") (pinfunction "GPIO.1/RS485_1") (pintype "passive+no_connect"))
    )
    (net (code "34") (name "/NC_GPIO2_CP2102") (class "Default")
      (node (ref "IC1") (pin "20") (pinfunction "GPIO.2/TXT_20") (pintype "passive+no_connect"))
    )
    (net (code "35") (name "/NC_GPIO3_CP2102") (class "Default")
      (node (ref "IC1") (pin "19") (pinfunction "GPIO.3/RXT_19") (pintype "passive+no_connect"))
    )
    (net (code "36") (name "/NC_Suspend_CP2102") (class "Default")
      (node (ref "IC1") (pin "14") (pinfunction "SUSPEND_14") (pintype "passive+no_connect"))
    )
    (net (code "37") (name "/NC_Wakeup_CP2102") (class "Default")
      (node (ref "IC1") (pin "13") (pinfunction "WAKEUP_13") (pintype "passive+no_connect"))
    )
    (net (code "38") (name "/NC_nSuspend_CP2102") (class "Default")
      (node (ref "IC1") (pin "11") (pinfunction "~{SUSPEND}_11") (pintype "passive+no_connect"))
    )
    (net (code "39") (name "/RTS_CP2102") (class "Default")
      (node (ref "IC1") (pin "16") (pinfunction "RTS_16") (pintype "passive"))
      (node (ref "TP3") (pin "1") (pinfunction "1_1") (pintype "passive"))
    )
    (net (code "40") (name "/RXD_CP2102") (class "Default")
      (node (ref "IC1") (pin "17") (pinfunction "RXD_17") (pintype "passive"))
      (node (ref "SW1") (pin "1") (pinfunction "NC_1") (pintype "passive"))
    )
    (net (code "41") (name "/Reset") (class "Default")
      (node (ref "S5") (pin "1") (pinfunction "1_1") (pintype "passive"))
      (node (ref "S5") (pin "2") (pinfunction "2_2") (pintype "passive"))
      (node (ref "X33") (pin "2") (pinfunction "2_2") (pintype "passive"))
    )
    (net (code "42") (name "/SPI_CLK") (class "Default")
      (node (ref "X14") (pin "1") (pinfunction "1_1") (pintype "passive"))
      (node (ref "X2") (pin "7") (pinfunction "7_7") (pintype "passive"))
    )
    (net (code "43") (name "/SPI_CS1") (class "Default")
      (node (ref "X12") (pin "1") (pinfunction "1_1") (pintype "passive"))
      (node (ref "X2") (pin "8") (pinfunction "8_8") (pintype "passive"))
    )
    (net (code "44") (name "/SPI_CS2") (class "Default")
      (node (ref "X10") (pin "1") (pinfunction "1_1") (pintype "passive"))
      (node (ref "X2") (pin "9") (pinfunction "9_9") (pintype "passive"))
    )
    (net (code "45") (name "/SPI_CS3") (class "Default")
      (node (ref "X2") (pin "10") (pinfunction "10_10") (pintype "passive"))
      (node (ref "X8") (pin "1") (pinfunction "1_1") (pintype "passive"))
    )
    (net (code "46") (name "/SPI_CS4") (class "Default")
      (node (ref "X2") (pin "11") (pinfunction "11_11") (pintype "passive"))
      (node (ref "X6") (pin "1") (pinfunction "1_1") (pintype "passive"))
    )
    (net (code "47") (name "/SPI_MISO") (class "Default")
      (node (ref "X16") (pin "1") (pinfunction "1_1") (pintype "passive"))
      (node (ref "X2") (pin "6") (pinfunction "6_6") (pintype "passive"))
    )
    (net (code "48") (name "/SPI_MOSI") (class "Default")
      (node (ref "X18") (pin "1") (pinfunction "1_1") (pintype "passive"))
      (node (ref "X2") (pin "5") (pinfunction "5_5") (pintype "passive"))
    )
    (net (code "49") (name "/SWCLK") (class "Default")
      (node (ref "X25") (pin "1") (pinfunction "1_1") (pintype "passive"))
      (node (ref "X45") (pin "4") (pinfunction "4_4") (pintype "passive"))
      (node (ref "X47") (pin "6") (pinfunction "6_6") (pintype "passive"))
    )
    (net (code "50") (name "/SWDIO") (class "Default")
      (node (ref "X25") (pin "2") (pinfunction "2_2") (pintype "passive"))
      (node (ref "X45") (pin "2") (pinfunction "2_2") (pintype "passive"))
      (node (ref "X47") (pin "4") (pinfunction "4_4") (pintype "passive"))
    )
    (net (code "51") (name "/SWO") (class "Default")
      (node (ref "X45") (pin "6") (pinfunction "6_6") (pintype "passive"))
      (node (ref "X47") (pin "8") (pinfunction "8_8") (pintype "passive"))
    )
    (net (code "52") (name "/TXD_CP2102") (class "Default")
      (node (ref "IC1") (pin "18") (pinfunction "TXD_18") (pintype "passive"))
      (node (ref "SW2") (pin "1") (pinfunction "NC_1") (pintype "passive"))
    )
    (net (code "53") (name "/UART1_CTS") (class "Default")
      (node (ref "X1") (pin "9") (pinfunction "9_9") (pintype "passive"))
      (node (ref "X9") (pin "1") (pinfunction "1_1") (pintype "passive"))
    )
    (net (code "54") (name "/UART1_RTS") (class "Default")
      (node (ref "X1") (pin "10") (pinfunction "10_10") (pintype "passive"))
      (node (ref "X7") (pin "1") (pinfunction "1_1") (pintype "passive"))
    )
    (net (code "55") (name "/UART1_RX") (class "Default")
      (node (ref "R19") (pin "2") (pinfunction "2_2") (pintype "passive"))
      (node (ref "X1") (pin "12") (pinfunction "12_12") (pintype "passive"))
      (node (ref "X3") (pin "1") (pinfunction "1_1") (pintype "passive"))
    )
    (net (code "56") (name "/UART1_TX") (class "Default")
      (node (ref "R18") (pin "2") (pinfunction "2_2") (pintype "passive"))
      (node (ref "X1") (pin "11") (pinfunction "11_11") (pintype "passive"))
      (node (ref "X5") (pin "1") (pinfunction "1_1") (pintype "passive"))
    )
    (net (code "57") (name "/UART2_RX") (class "Default")
      (node (ref "X1") (pin "8") (pinfunction "8_8") (pintype "passive"))
      (node (ref "X11") (pin "1") (pinfunction "1_1") (pintype "passive"))
    )
    (net (code "58") (name "/UART2_TX") (class "Default")
      (node (ref "X1") (pin "7") (pinfunction "7_7") (pintype "passive"))
      (node (ref "X13") (pin "1") (pinfunction "1_1") (pintype "passive"))
    )
    (net (code "59") (name "/USB_0_D1_N") (class "Default")
      (node (ref "R22") (pin "2") (pinfunction "2_2") (pintype "passive"))
      (node (ref "X1") (pin "2") (pinfunction "2_2") (pintype "passive"))
    )
    (net (code "60") (name "/USB_0_D1_P") (class "Default")
      (node (ref "R23") (pin "2") (pinfunction "2_2") (pintype "passive"))
      (node (ref "X1") (pin "1") (pinfunction "1_1") (pintype "passive"))
    )
    (net (code "61") (name "/USB_0_D_N") (class "Default")
      (node (ref "D6") (pin "1") (pinfunction "D1+_1") (pintype "passive"))
      (node (ref "D6") (pin "10") (pinfunction "NC_10") (pintype "passive"))
      (node (ref "R22") (pin "1") (pinfunction "1_1") (pintype "passive"))
      (node (ref "X44") (pin "2") (pinfunction "D-_2") (pintype "passive"))
    )
    (net (code "62") (name "/USB_0_D_P") (class "Default")
      (node (ref "D6") (pin "2") (pinfunction "D1-_2") (pintype "passive"))
      (node (ref "D6") (pin "9") (pinfunction "NC_9") (pintype "passive"))
      (node (ref "R23") (pin "1") (pinfunction "1_1") (pintype "passive"))
      (node (ref "X44") (pin "3") (pinfunction "D+_3") (pintype "passive"))
    )
    (net (code "63") (name "/VBUS_CP2102") (class "Default")
      (node (ref "IC1") (pin "8") (pinfunction "VBUS_8") (pintype "passive"))
      (node (ref "R16") (pin "1") (pinfunction "1_1") (pintype "passive"))
      (node (ref "R17") (pin "2") (pinfunction "2_2") (pintype "passive"))
    )
    (net (code "64") (name "/VCP_RX") (class "Default")
      (node (ref "SW1") (pin "3") (pinfunction "NO_3") (pintype "passive"))
      (node (ref "X47") (pin "13") (pinfunction "13_13") (pintype "passive"))
    )
    (net (code "65") (name "/VCP_TX") (class "Default")
      (node (ref "SW2") (pin "3") (pinfunction "NO_3") (pintype "passive"))
      (node (ref "X47") (pin "14") (pinfunction "14_14") (pintype "passive"))
    )
    (net (code "66") (name "/VDD_CP2102") (class "Default")
      (node (ref "C11") (pin "2") (pinfunction "2_2") (pintype "passive"))
      (node (ref "C12") (pin "2") (pinfunction "2_2") (pintype "passive"))
      (node (ref "IC1") (pin "6") (pinfunction "VDD_6") (pintype "passive"))
      (node (ref "R15") (pin "1") (pinfunction "1_1") (pintype "passive"))
    )
    (net (code "67") (name "/nRESET") (class "Default")
      (node (ref "X45") (pin "10") (pinfunction "10_10") (pintype "passive"))
      (node (ref "X47") (pin "12") (pinfunction "12_12") (pintype "passive"))
    )
    (net (code "68") (name "/nRST_CP2102") (class "Default")
      (node (ref "IC1") (pin "9") (pinfunction "~{RST}_9") (pintype "passive"))
      (node (ref "R15") (pin "2") (pinfunction "2_2") (pintype "passive"))
    )
    (net (code "69") (name "3V3") (class "Default")
      (node (ref "C6") (pin "2") (pinfunction "2_2") (pintype "passive"))
      (node (ref "C9") (pin "1") (pinfunction "1_1") (pintype "passive"))
      (node (ref "L1") (pin "1") (pinfunction "1_1") (pintype "passive"))
      (node (ref "R1") (pin "2") (pinfunction "2_2") (pintype "passive"))
      (node (ref "R10") (pin "1") (pinfunction "1_1") (pintype "passive"))
      (node (ref "R11") (pin "2") (pinfunction "2_2") (pintype "passive"))
      (node (ref "R14") (pin "2") (pinfunction "2_2") (pintype "passive"))
      (node (ref "R2") (pin "2") (pinfunction "2_2") (pintype "passive"))
      (node (ref "R3") (pin "1") (pinfunction "1_1") (pintype "passive"))
      (node (ref "R4") (pin "1") (pinfunction "1_1") (pintype "passive"))
      (node (ref "R7") (pin "1") (pinfunction "1_1") (pintype "passive"))
      (node (ref "R8") (pin "2") (pinfunction "2_2") (pintype "passive"))
      (node (ref "R9") (pin "1") (pinfunction "1_1") (pintype "passive"))
      (node (ref "VR1") (pin "2") (pinfunction "Vout_2") (pintype "passive"))
      (node (ref "X33") (pin "5") (pinfunction "5_5") (pintype "passive"))
      (node (ref "X41") (pin "1") (pinfunction "1_1") (pintype "passive"))
      (node (ref "X45") (pin "1") (pinfunction "1_1") (pintype "passive"))
      (node (ref "X47") (pin "3") (pinfunction "3_3") (pintype "passive"))
      (node (ref "X49") (pin "1") (pinfunction "1_1") (pintype "passive"))
      (node (ref "X50") (pin "1") (pinfunction "1_1") (pintype "passive"))
      (node (ref "X51") (pin "1") (pinfunction "1_1") (pintype "passive"))
    )
    (net (code "70") (name "3V3A") (class "Default")
      (node (ref "C10") (pin "1") (pinfunction "1_1") (pintype "passive"))
      (node (ref "L1") (pin "2") (pinfunction "2_2") (pintype "passive"))
      (node (ref "R13") (pin "3") (pinfunction "3_3") (pintype "passive"))
      (node (ref "R6") (pin "3") (pinfunction "3_3") (pintype "passive"))
      (node (ref "X33") (pin "4") (pinfunction "4_4") (pintype "passive"))
      (node (ref "X41") (pin "2") (pinfunction "2_2") (pintype "passive"))
      (node (ref "X48") (pin "1") (pinfunction "1_1") (pintype "passive"))
    )
    (net (code "71") (name "5V0") (class "Default")
      (node (ref "C5") (pin "2") (pinfunction "2_2") (pintype "passive"))
      (node (ref "L3") (pin "1") (pinfunction "1_1") (pintype "passive"))
      (node (ref "VR1") (pin "3") (pinfunction "Vin_3") (pintype "passive"))
      (node (ref "X43") (pin "1") (pinfunction "1_1") (pintype "passive"))
    )
    (net (code "72") (name "GND") (class "Default")
      (node (ref "C1") (pin "2") (pinfunction "2_2") (pintype "passive"))
      (node (ref "C10") (pin "2") (pinfunction "2_2") (pintype "passive"))
      (node (ref "C11") (pin "1") (pinfunction "1_1") (pintype "passive"))
      (node (ref "C12") (pin "1") (pinfunction "1_1") (pintype "passive"))
      (node (ref "C13") (pin "1") (pinfunction "1_1") (pintype "passive"))
      (node (ref "C14") (pin "1") (pinfunction "1_1") (pintype "passive"))
      (node (ref "C2") (pin "2") (pinfunction "2_2") (pintype "passive"))
      (node (ref "C3") (pin "2") (pinfunction "2_2") (pintype "passive"))
      (node (ref "C4") (pin "2") (pinfunction "2_2") (pintype "passive"))
      (node (ref "C5") (pin "1") (pinfunction "1_1") (pintype "passive"))
      (node (ref "C6") (pin "1") (pinfunction "1_1") (pintype "passive"))
      (node (ref "C7") (pin "2") (pinfunction "2_2") (pintype "passive"))
      (node (ref "C8") (pin "2") (pinfunction "2_2") (pintype "passive"))
      (node (ref "C9") (pin "2") (pinfunction "2_2") (pintype "passive"))
      (node (ref "D5") (pin "K") (pinfunction "K_K") (pintype "passive"))
      (node (ref "D6") (pin "3") (pinfunction "GND_3") (pintype "power_in"))
      (node (ref "D6") (pin "8") (pinfunction "GND_8") (pintype "power_in"))
      (node (ref "D7") (pin "3") (pinfunction "GND_3") (pintype "power_in"))
      (node (ref "D7") (pin "8") (pinfunction "GND_8") (pintype "power_in"))
      (node (ref "D8") (pin "A") (pinfunction "A_A") (pintype "passive"))
      (node (ref "D9") (pin "A") (pinfunction "A_A") (pintype "passive"))
      (node (ref "IC1") (pin "12") (pinfunction "GND_12") (pintype "passive"))
      (node (ref "IC1") (pin "21") (pinfunction "GND_21") (pintype "passive"))
      (node (ref "IC1") (pin "3") (pinfunction "GND_3") (pintype "passive"))
      (node (ref "R13") (pin "1") (pinfunction "1_1") (pintype "passive"))
      (node (ref "R16") (pin "2") (pinfunction "2_2") (pintype "passive"))
      (node (ref "R6") (pin "1") (pinfunction "1_1") (pintype "passive"))
      (node (ref "S1") (pin "3") (pinfunction "3_3") (pintype "passive"))
      (node (ref "S1") (pin "4") (pinfunction "4_4") (pintype "passive"))
      (node (ref "S2") (pin "3") (pinfunction "3_3") (pintype "passive"))
      (node (ref "S2") (pin "4") (pinfunction "4_4") (pintype "passive"))
      (node (ref "S3") (pin "3") (pinfunction "3_3") (pintype "passive"))
      (node (ref "S3") (pin "4") (pinfunction "4_4") (pintype "passive"))
      (node (ref "S4") (pin "3") (pinfunction "3_3") (pintype "passive"))
      (node (ref "S4") (pin "4") (pinfunction "4_4") (pintype "passive"))
      (node (ref "S5") (pin "3") (pinfunction "3_3") (pintype "passive"))
      (node (ref "S5") (pin "4") (pinfunction "4_4") (pintype "passive"))
      (node (ref "VR1") (pin "1") (pinfunction "GND_1") (pintype "passive"))
      (node (ref "X33") (pin "1") (pinfunction "1_1") (pintype "passive"))
      (node (ref "X33") (pin "3") (pinfunction "3_3") (pintype "passive"))
      (node (ref "X42") (pin "2") (pinfunction "2_2") (pintype "passive"))
      (node (ref "X44") (pin "4") (pinfunction "ID_4") (pintype "passive"))
      (node (ref "X44") (pin "5") (pinfunction "GND_5") (pintype "power_in"))
      (node (ref "X44") (pin "6") (pinfunction "Shield_6") (pintype "power_in"))
      (node (ref "X45") (pin "3") (pinfunction "3_3") (pintype "passive"))
      (node (ref "X45") (pin "5") (pinfunction "5_5") (pintype "passive"))
      (node (ref "X45") (pin "9") (pinfunction "9_9") (pintype "passive"))
      (node (ref "X46") (pin "4") (pinfunction "ID_4") (pintype "passive"))
      (node (ref "X46") (pin "5") (pinfunction "GND_5") (pintype "power_in"))
      (node (ref "X46") (pin "6") (pinfunction "Shield_6") (pintype "power_in"))
      (node (ref "X47") (pin "11") (pinfunction "11_11") (pintype "passive"))
      (node (ref "X47") (pin "5") (pinfunction "5_5") (pintype "passive"))
      (node (ref "X47") (pin "7") (pinfunction "7_7") (pintype "passive"))
      (node (ref "X52") (pin "1") (pinfunction "1_1") (pintype "passive"))
      (node (ref "X53") (pin "1") (pinfunction "1_1") (pintype "passive"))
      (node (ref "X54") (pin "1") (pinfunction "1_1") (pintype "passive"))
      (node (ref "X55") (pin "1") (pinfunction "1_1") (pintype "passive"))
      (node (ref "X56") (pin "1") (pinfunction "1_1") (pintype "passive"))
      (node (ref "X57") (pin "1") (pinfunction "1_1") (pintype "passive"))
      (node (ref "X58") (pin "1") (pinfunction "1_1") (pintype "passive"))
      (node (ref "X59") (pin "1") (pinfunction "1_1") (pintype "passive"))
      (node (ref "X60") (pin "1") (pinfunction "1_1") (pintype "passive"))
      (node (ref "X61") (pin "1") (pinfunction "1_1") (pintype "passive"))
      (node (ref "X62") (pin "1") (pinfunction "1_1") (pintype "passive"))
      (node (ref "X63") (pin "1") (pinfunction "1_1") (pintype "passive"))
      (node (ref "X64") (pin "1") (pinfunction "1_1") (pintype "passive"))
      (node (ref "X65") (pin "1") (pinfunction "1_1") (pintype "passive"))
    )
    (net (code "73") (name "Net-(C3-Pad1)") (class "Default")
      (node (ref "C3") (pin "1") (pinfunction "1_1") (pintype "passive"))
      (node (ref "R20") (pin "1") (pinfunction "1_1") (pintype "passive"))
      (node (ref "R5") (pin "1") (pinfunction "1_1") (pintype "passive"))
    )
    (net (code "74") (name "Net-(C7-Pad1)") (class "Default")
      (node (ref "C7") (pin "1") (pinfunction "1_1") (pintype "passive"))
      (node (ref "R12") (pin "1") (pinfunction "1_1") (pintype "passive"))
      (node (ref "R21") (pin "1") (pinfunction "1_1") (pintype "passive"))
    )
    (net (code "75") (name "Net-(D1-PadA)") (class "Default")
      (node (ref "D1") (pin "A") (pinfunction "A_A") (pintype "passive"))
      (node (ref "R3") (pin "2") (pinfunction "2_2") (pintype "passive"))
    )
    (net (code "76") (name "Net-(D2-PadA)") (class "Default")
      (node (ref "D2") (pin "A") (pinfunction "A_A") (pintype "passive"))
      (node (ref "R4") (pin "2") (pinfunction "2_2") (pintype "passive"))
    )
    (net (code "77") (name "Net-(D3-PadA)") (class "Default")
      (node (ref "D3") (pin "A") (pinfunction "A_A") (pintype "passive"))
      (node (ref "R7") (pin "2") (pinfunction "2_2") (pintype "passive"))
    )
    (net (code "78") (name "Net-(D4-PadA)") (class "Default")
      (node (ref "D4") (pin "A") (pinfunction "A_A") (pintype "passive"))
      (node (ref "R9") (pin "2") (pinfunction "2_2") (pintype "passive"))
    )
    (net (code "79") (name "Net-(D5-PadA)") (class "Default")
      (node (ref "D5") (pin "A") (pinfunction "A_A") (pintype "passive"))
      (node (ref "R10") (pin "2") (pinfunction "2_2") (pintype "passive"))
    )
    (net (code "80") (name "Net-(L2-Pad1)") (class "Default")
      (node (ref "L2") (pin "1") (pinfunction "1_1") (pintype "passive"))
      (node (ref "X43") (pin "2") (pinfunction "2_2") (pintype "passive"))
    )
    (net (code "81") (name "Net-(R5-Pad2)") (class "Default")
      (node (ref "R5") (pin "2") (pinfunction "2_2") (pintype "passive"))
      (node (ref "R6") (pin "2") (pinfunction "2_2") (pintype "passive"))
    )
    (net (code "82") (name "Net-(R12-Pad2)") (class "Default")
      (node (ref "R12") (pin "2") (pinfunction "2_2") (pintype "passive"))
      (node (ref "R13") (pin "2") (pinfunction "2_2") (pintype "passive"))
    )
    (net (code "83") (name "Net-(SW1-COM)") (class "Default")
      (node (ref "R18") (pin "1") (pinfunction "1_1") (pintype "passive"))
      (node (ref "SW1") (pin "2") (pinfunction "COM_2") (pintype "passive"))
    )
    (net (code "84") (name "Net-(SW2-COM)") (class "Default")
      (node (ref "R19") (pin "1") (pinfunction "1_1") (pintype "passive"))
      (node (ref "SW2") (pin "2") (pinfunction "COM_2") (pintype "passive"))
    )
    (net (code "85") (name "Net-(X44-VBUS)") (class "Default")
      (node (ref "D8") (pin "K") (pinfunction "K_K") (pintype "passive"))
      (node (ref "L2") (pin "2") (pinfunction "2_2") (pintype "passive"))
      (node (ref "X44") (pin "1") (pinfunction "VBUS_1") (pintype "power_in"))
    )
    (net (code "86") (name "Net-(X46-VBUS)") (class "Default")
      (node (ref "D9") (pin "K") (pinfunction "K_K") (pintype "passive"))
      (node (ref "L3") (pin "2") (pinfunction "2_2") (pintype "passive"))
      (node (ref "X46") (pin "1") (pinfunction "VBUS_1") (pintype "power_in"))
    )
    (net (code "87") (name "VBUS") (class "Default")
      (node (ref "C13") (pin "2") (pinfunction "2_2") (pintype "passive"))
      (node (ref "C14") (pin "2") (pinfunction "2_2") (pintype "passive"))
      (node (ref "IC1") (pin "7") (pinfunction "VREGIN_7") (pintype "passive"))
      (node (ref "R17") (pin "1") (pinfunction "1_1") (pintype "passive"))
    )
    (net (code "88") (name "unconnected-(D6-D2+-Pad4)") (class "Default")
      (node (ref "D6") (pin "4") (pinfunction "D2+_4") (pintype "passive+no_connect"))
    )
    (net (code "89") (name "unconnected-(D6-D2--Pad5)") (class "Default")
      (node (ref "D6") (pin "5") (pinfunction "D2-_5") (pintype "passive+no_connect"))
    )
    (net (code "90") (name "unconnected-(D6-NC-Pad6)") (class "Default")
      (node (ref "D6") (pin "6") (pinfunction "NC_6") (pintype "passive+no_connect"))
    )
    (net (code "91") (name "unconnected-(D6-NC-Pad7)") (class "Default")
      (node (ref "D6") (pin "7") (pinfunction "NC_7") (pintype "passive+no_connect"))
    )
    (net (code "92") (name "unconnected-(D7-D2+-Pad4)") (class "Default")
      (node (ref "D7") (pin "4") (pinfunction "D2+_4") (pintype "passive+no_connect"))
    )
    (net (code "93") (name "unconnected-(D7-D2--Pad5)") (class "Default")
      (node (ref "D7") (pin "5") (pinfunction "D2-_5") (pintype "passive+no_connect"))
    )
    (net (code "94") (name "unconnected-(D7-NC-Pad6)") (class "Default")
      (node (ref "D7") (pin "6") (pinfunction "NC_6") (pintype "passive+no_connect"))
    )
    (net (code "95") (name "unconnected-(D7-NC-Pad7)") (class "Default")
      (node (ref "D7") (pin "7") (pinfunction "NC_7") (pintype "passive+no_connect"))
    )
  )
)
